# SMD_Breakout_LargeHeader.net
KiCad netlist of a schematic drawn in EAGLE
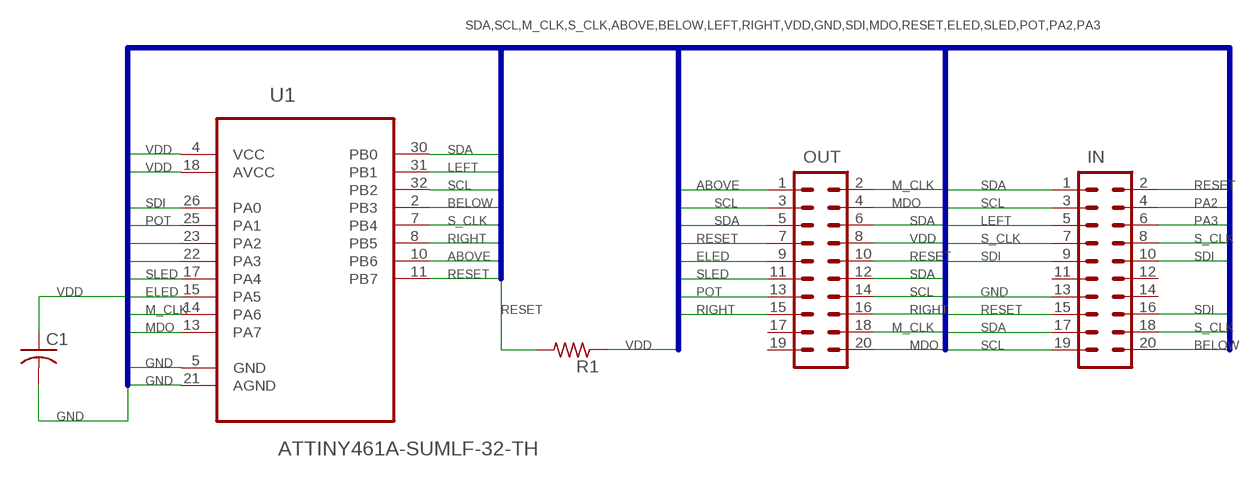
[diagram p0: schematic, sheet 1]

(export (version "E")
  (design (tool "Eeschema 10.0.6"))
  (components
    (comp (ref "C1")
      (value "C-USC0603")
      (footprint "eagle-import:C0603")
      (libsource (lib "eagle-import") (part "C-USC0603"))
    )
    (comp (ref "IN")
      (value "M10X2")
      (footprint "eagle-import:2X10")
      (libsource (lib "eagle-import") (part "M10X2"))
    )
    (comp (ref "OUT")
      (value "M10X2")
      (footprint "eagle-import:2X10")
      (libsource (lib "eagle-import") (part "M10X2"))
    )
    (comp (ref "R1")
      (value "R-US_R0603")
      (footprint "eagle-import:R0603")
      (libsource (lib "eagle-import") (part "R-US_R0603"))
    )
    (comp (ref "U1")
      (value "ATTINY461A-SUMLF-32-TH")
      (footprint "eagle-import:MLF32-TH")
      (libsource (lib "eagle-import") (part "ATTINY461A-SUMLF-32-TH"))
    )
  )
  (nets
    (net (code "1") (name "/ABOVE") (class "Default")
      (node (ref "OUT") (pin "1") (pinfunction "1_1") (pintype "passive"))
      (node (ref "U1") (pin "10") (pinfunction "PB6_10") (pintype "bidirectional"))
    )
    (net (code "2") (name "/BELOW") (class "Default")
      (node (ref "IN") (pin "20") (pinfunction "20_20") (pintype "passive"))
      (node (ref "U1") (pin "2") (pinfunction "PB3_2") (pintype "bidirectional"))
    )
    (net (code "3") (name "/ELED") (class "Default")
      (node (ref "OUT") (pin "9") (pinfunction "9_9") (pintype "passive"))
      (node (ref "U1") (pin "15") (pinfunction "PA5_15") (pintype "bidirectional"))
    )
    (net (code "4") (name "/GND") (class "Default")
      (node (ref "C1") (pin "2") (pinfunction "2_2") (pintype "passive"))
      (node (ref "IN") (pin "13") (pinfunction "13_13") (pintype "passive"))
      (node (ref "U1") (pin "21") (pinfunction "AGND_21") (pintype "passive"))
      (node (ref "U1") (pin "5") (pinfunction "GND_5") (pintype "passive"))
    )
    (net (code "5") (name "/LEFT") (class "Default")
      (node (ref "IN") (pin "5") (pinfunction "5_5") (pintype "passive"))
      (node (ref "U1") (pin "31") (pinfunction "PB1_31") (pintype "bidirectional"))
    )
    (net (code "6") (name "/MDO") (class "Default")
      (node (ref "OUT") (pin "20") (pinfunction "20_20") (pintype "passive"))
      (node (ref "OUT") (pin "4") (pinfunction "4_4") (pintype "passive"))
      (node (ref "U1") (pin "13") (pinfunction "PA7_13") (pintype "bidirectional"))
    )
    (net (code "7") (name "/M_CLK") (class "Default")
      (node (ref "OUT") (pin "18") (pinfunction "18_18") (pintype "passive"))
      (node (ref "OUT") (pin "2") (pinfunction "2_2") (pintype "passive"))
      (node (ref "U1") (pin "14") (pinfunction "PA6_14") (pintype "bidirectional"))
    )
    (net (code "8") (name "/PA2") (class "Default")
      (node (ref "IN") (pin "4") (pinfunction "4_4") (pintype "passive"))
      (node (ref "U1") (pin "23") (pinfunction "PA2_23") (pintype "bidirectional"))
    )
    (net (code "9") (name "/PA3") (class "Default")
      (node (ref "IN") (pin "6") (pinfunction "6_6") (pintype "passive"))
      (node (ref "U1") (pin "22") (pinfunction "PA3_22") (pintype "bidirectional"))
    )
    (net (code "10") (name "/POT") (class "Default")
      (node (ref "OUT") (pin "13") (pinfunction "13_13") (pintype "passive"))
      (node (ref "U1") (pin "25") (pinfunction "PA1_25") (pintype "bidirectional"))
    )
    (net (code "11") (name "/RESET") (class "Default")
      (node (ref "IN") (pin "15") (pinfunction "15_15") (pintype "passive"))
      (node (ref "IN") (pin "2") (pinfunction "2_2") (pintype "passive"))
      (node (ref "OUT") (pin "10") (pinfunction "10_10") (pintype "passive"))
      (node (ref "OUT") (pin "7") (pinfunction "7_7") (pintype "passive"))
      (node (ref "R1") (pin "2") (pinfunction "2_2") (pintype "passive"))
      (node (ref "U1") (pin "11") (pinfunction "PB7_11") (pintype "bidirectional"))
    )
    (net (code "12") (name "/RIGHT") (class "Default")
      (node (ref "OUT") (pin "15") (pinfunction "15_15") (pintype "passive"))
      (node (ref "OUT") (pin "16") (pinfunction "16_16") (pintype "passive"))
      (node (ref "U1") (pin "8") (pinfunction "PB5_8") (pintype "bidirectional"))
    )
    (net (code "13") (name "/SCL") (class "Default")
      (node (ref "IN") (pin "19") (pinfunction "19_19") (pintype "passive"))
      (node (ref "IN") (pin "3") (pinfunction "3_3") (pintype "passive"))
      (node (ref "OUT") (pin "14") (pinfunction "14_14") (pintype "passive"))
      (node (ref "OUT") (pin "3") (pinfunction "3_3") (pintype "passive"))
      (node (ref "U1") (pin "32") (pinfunction "PB2_32") (pintype "bidirectional"))
    )
    (net (code "14") (name "/SDA") (class "Default")
      (node (ref "IN") (pin "1") (pinfunction "1_1") (pintype "passive"))
      (node (ref "IN") (pin "17") (pinfunction "17_17") (pintype "passive"))
      (node (ref "OUT") (pin "12") (pinfunction "12_12") (pintype "passive"))
      (node (ref "OUT") (pin "5") (pinfunction "5_5") (pintype "passive"))
      (node (ref "OUT") (pin "6") (pinfunction "6_6") (pintype "passive"))
      (node (ref "U1") (pin "30") (pinfunction "PB0_30") (pintype "bidirectional"))
    )
    (net (code "15") (name "/SDI") (class "Default")
      (node (ref "IN") (pin "10") (pinfunction "10_10") (pintype "passive"))
      (node (ref "IN") (pin "16") (pinfunction "16_16") (pintype "passive"))
      (node (ref "IN") (pin "9") (pinfunction "9_9") (pintype "passive"))
      (node (ref "U1") (pin "26") (pinfunction "PA0_26") (pintype "bidirectional"))
    )
    (net (code "16") (name "/SLED") (class "Default")
      (node (ref "OUT") (pin "11") (pinfunction "11_11") (pintype "passive"))
      (node (ref "U1") (pin "17") (pinfunction "PA4_17") (pintype "bidirectional"))
    )
    (net (code "17") (name "/S_CLK") (class "Default")
      (node (ref "IN") (pin "18") (pinfunction "18_18") (pintype "passive"))
      (node (ref "IN") (pin "7") (pinfunction "7_7") (pintype "passive"))
      (node (ref "IN") (pin "8") (pinfunction "8_8") (pintype "passive"))
      (node (ref "U1") (pin "7") (pinfunction "PB4_7") (pintype "bidirectional"))
    )
    (net (code "18") (name "/VDD") (class "Default")
      (node (ref "C1") (pin "1") (pinfunction "1_1") (pintype "passive"))
      (node (ref "OUT") (pin "8") (pinfunction "8_8") (pintype "passive"))
      (node (ref "R1") (pin "1") (pinfunction "1_1") (pintype "passive"))
      (node (ref "U1") (pin "18") (pinfunction "AVCC_18") (pintype "power_in"))
      (node (ref "U1") (pin "4") (pinfunction "VCC_4") (pintype "power_in"))
    )
    (net (code "20") (name "unconnected-(IN-Pad11)") (class "Default")
      (node (ref "IN") (pin "11") (pinfunction "11_11") (pintype "passive"))
    )
    (net (code "21") (name "unconnected-(IN-Pad12)") (class "Default")
      (node (ref "IN") (pin "12") (pinfunction "12_12") (pintype "passive"))
    )
    (net (code "22") (name "unconnected-(IN-Pad14)") (class "Default")
      (node (ref "IN") (pin "14") (pinfunction "14_14") (pintype "passive"))
    )
    (net (code "23") (name "unconnected-(OUT-Pad17)") (class "Default")
      (node (ref "OUT") (pin "17") (pinfunction "17_17") (pintype "passive"))
    )
    (net (code "24") (name "unconnected-(OUT-Pad19)") (class "Default")
      (node (ref "OUT") (pin "19") (pinfunction "19_19") (pintype "passive"))
    )
  )
)
